# Arduino.net
KiCad netlist of a schematic drawn in EasyEDA Pro
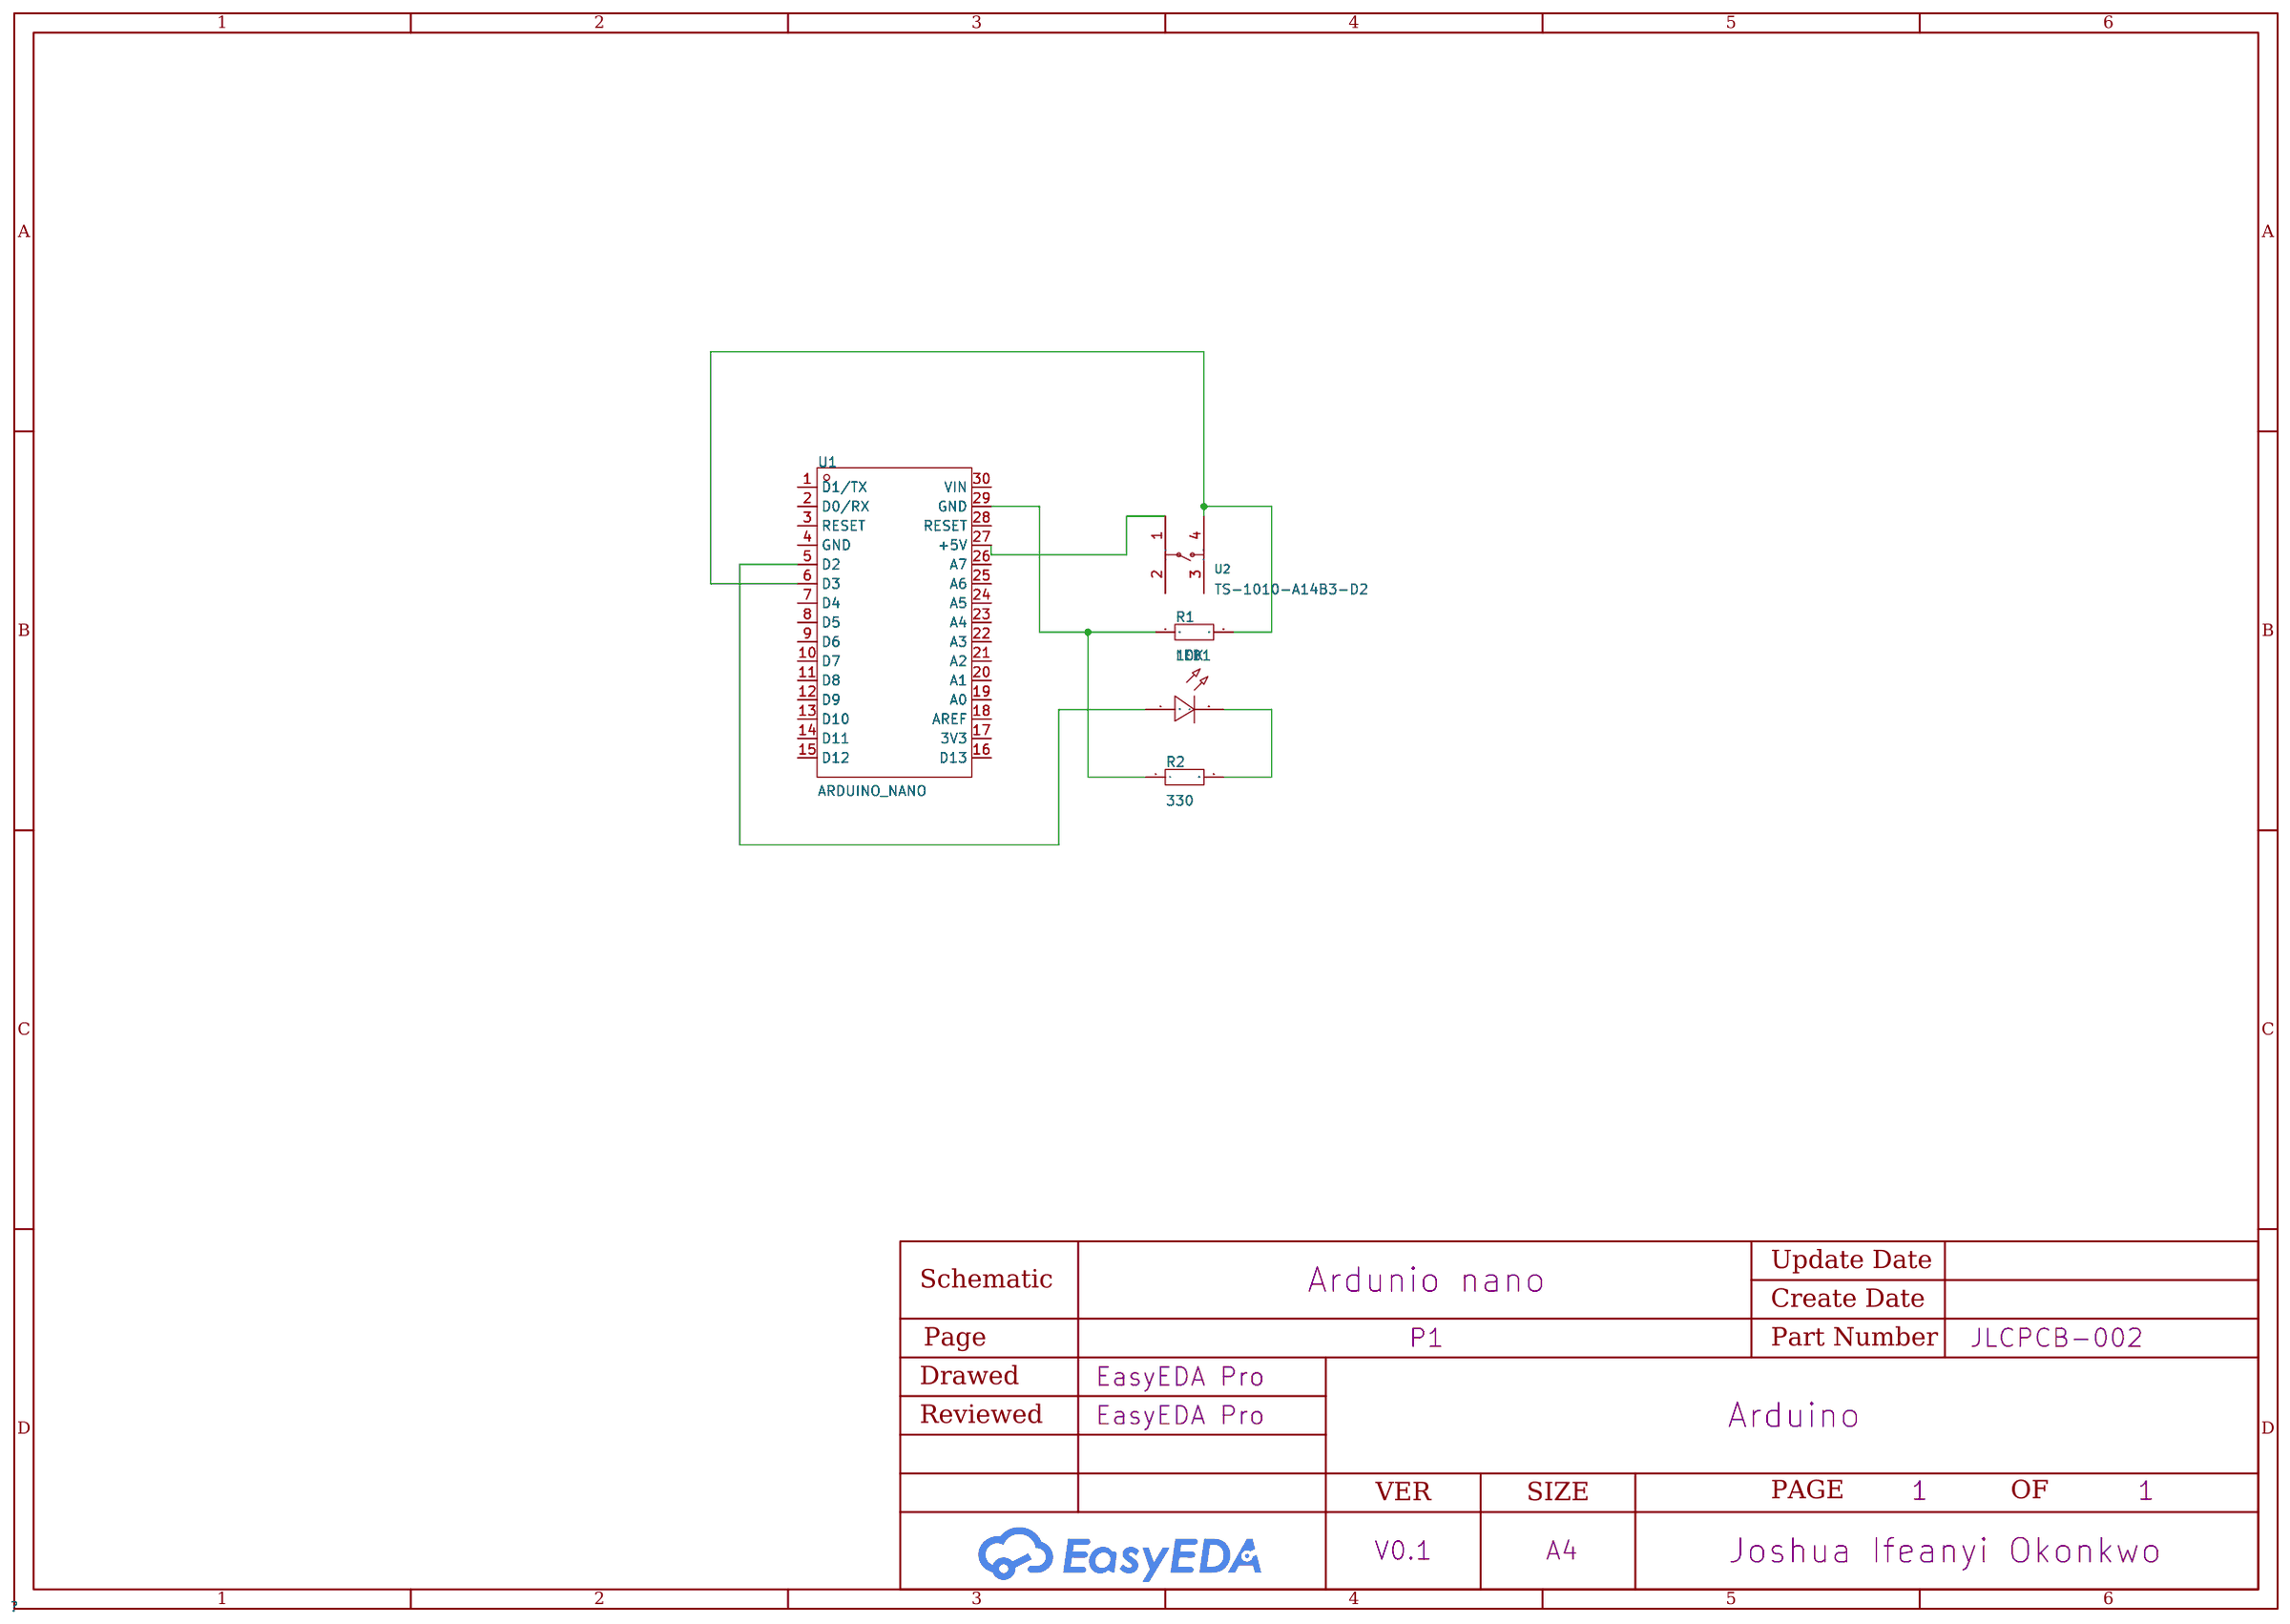
[diagram p0: schematic sheet]

(export (version "E")
  (design (tool "Eeschema 10.0.6"))
  (components
    (comp (ref "LED1")
      (value "~")
      (footprint "easyedapro:LED-TH_BD3.0-P2.54-FD")
      (libsource (lib "easyedapro") (part "LED_TH-R"))
    )
    (comp (ref "R1") (value "10K") (footprint "easyedapro:R0603") (libsource (lib "easyedapro") (part "Res")))
    (comp (ref "R2") (value "330") (footprint "easyedapro:R0603") (libsource (lib "easyedapro") (part "Res")))
    (comp (ref "U1")
      (value "ARDUINO_NANO")
      (footprint "easyedapro:COMM-TH_ARDUINO_NANO")
      (libsource (lib "easyedapro") (part "ARDUINO_NANO"))
    )
    (comp (ref "U2")
      (value "TS-1010-A14B3-D2")
      (footprint "easyedapro:SW-TH_4P-L6.2-W6.2-P4.50-LS6.5")
      (fields (field (name "Manufacturer") "Yuandi(元迪)"))
      (libsource (lib "easyedapro") (part "TS-1010-A14B3-D2"))
    )
  )
  (nets
    (net (code "1") (name "Net-(LED1-A)") (class "Default")
      (node (ref "LED1") (pin "2") (pinfunction "A_2") (pintype "input"))
      (node (ref "R2") (pin "2") (pinfunction "2_2") (pintype "input"))
    )
    (net (code "2") (name "Net-(LED1-C)") (class "Default")
      (node (ref "LED1") (pin "1") (pinfunction "C_1") (pintype "input"))
      (node (ref "U1") (pin "5") (pinfunction "D2_5") (pintype "input"))
    )
    (net (code "3") (name "Net-(R1-Pad1)") (class "Default")
      (node (ref "R1") (pin "1") (pinfunction "1_1") (pintype "input"))
      (node (ref "R2") (pin "1") (pinfunction "1_1") (pintype "input"))
      (node (ref "U1") (pin "29") (pinfunction "GND_29") (pintype "input"))
    )
    (net (code "4") (name "Net-(U1-+5V)") (class "Default")
      (node (ref "U1") (pin "27") (pinfunction "+5V_27") (pintype "input"))
      (node (ref "U2") (pin "1") (pinfunction "1_1") (pintype "input"))
    )
    (net (code "5") (name "Net-(U1-D3)") (class "Default")
      (node (ref "R1") (pin "2") (pinfunction "2_2") (pintype "input"))
      (node (ref "U1") (pin "6") (pinfunction "D3_6") (pintype "input"))
      (node (ref "U2") (pin "4") (pinfunction "4_4") (pintype "input"))
    )
    (net (code "6") (name "unconnected-(U1-3V3-Pad17)") (class "Default")
      (node (ref "U1") (pin "17") (pinfunction "3V3_17") (pintype "input"))
    )
    (net (code "7") (name "unconnected-(U1-A0-Pad19)") (class "Default")
      (node (ref "U1") (pin "19") (pinfunction "A0_19") (pintype "input"))
    )
    (net (code "8") (name "unconnected-(U1-A1-Pad20)") (class "Default")
      (node (ref "U1") (pin "20") (pinfunction "A1_20") (pintype "input"))
    )
    (net (code "9") (name "unconnected-(U1-A2-Pad21)") (class "Default")
      (node (ref "U1") (pin "21") (pinfunction "A2_21") (pintype "input"))
    )
    (net (code "10") (name "unconnected-(U1-A3-Pad22)") (class "Default")
      (node (ref "U1") (pin "22") (pinfunction "A3_22") (pintype "input"))
    )
    (net (code "11") (name "unconnected-(U1-A4-Pad23)") (class "Default")
      (node (ref "U1") (pin "23") (pinfunction "A4_23") (pintype "input"))
    )
    (net (code "12") (name "unconnected-(U1-A5-Pad24)") (class "Default")
      (node (ref "U1") (pin "24") (pinfunction "A5_24") (pintype "input"))
    )
    (net (code "13") (name "unconnected-(U1-A6-Pad25)") (class "Default")
      (node (ref "U1") (pin "25") (pinfunction "A6_25") (pintype "input"))
    )
    (net (code "14") (name "unconnected-(U1-A7-Pad26)") (class "Default")
      (node (ref "U1") (pin "26") (pinfunction "A7_26") (pintype "input"))
    )
    (net (code "15") (name "unconnected-(U1-AREF-Pad18)") (class "Default")
      (node (ref "U1") (pin "18") (pinfunction "AREF_18") (pintype "input"))
    )
    (net (code "16") (name "unconnected-(U1-D0{slash}RX-Pad2)") (class "Default")
      (node (ref "U1") (pin "2") (pinfunction "D0/RX_2") (pintype "input"))
    )
    (net (code "17") (name "unconnected-(U1-D1{slash}TX-Pad1)") (class "Default")
      (node (ref "U1") (pin "1") (pinfunction "D1/TX_1") (pintype "input"))
    )
    (net (code "18") (name "unconnected-(U1-D4-Pad7)") (class "Default")
      (node (ref "U1") (pin "7") (pinfunction "D4_7") (pintype "input"))
    )
    (net (code "19") (name "unconnected-(U1-D5-Pad8)") (class "Default")
      (node (ref "U1") (pin "8") (pinfunction "D5_8") (pintype "input"))
    )
    (net (code "20") (name "unconnected-(U1-D6-Pad9)") (class "Default")
      (node (ref "U1") (pin "9") (pinfunction "D6_9") (pintype "input"))
    )
    (net (code "21") (name "unconnected-(U1-D7-Pad10)") (class "Default")
      (node (ref "U1") (pin "10") (pinfunction "D7_10") (pintype "input"))
    )
    (net (code "22") (name "unconnected-(U1-D8-Pad11)") (class "Default")
      (node (ref "U1") (pin "11") (pinfunction "D8_11") (pintype "input"))
    )
    (net (code "23") (name "unconnected-(U1-D9-Pad12)") (class "Default")
      (node (ref "U1") (pin "12") (pinfunction "D9_12") (pintype "input"))
    )
    (net (code "24") (name "unconnected-(U1-D10-Pad13)") (class "Default")
      (node (ref "U1") (pin "13") (pinfunction "D10_13") (pintype "input"))
    )
    (net (code "25") (name "unconnected-(U1-D11-Pad14)") (class "Default")
      (node (ref "U1") (pin "14") (pinfunction "D11_14") (pintype "input"))
    )
    (net (code "26") (name "unconnected-(U1-D12-Pad15)") (class "Default")
      (node (ref "U1") (pin "15") (pinfunction "D12_15") (pintype "input"))
    )
    (net (code "27") (name "unconnected-(U1-D13-Pad16)") (class "Default")
      (node (ref "U1") (pin "16") (pinfunction "D13_16") (pintype "input"))
    )
    (net (code "28") (name "unconnected-(U1-GND-Pad4)") (class "Default")
      (node (ref "U1") (pin "4") (pinfunction "GND_4") (pintype "input"))
    )
    (net (code "29") (name "unconnected-(U1-RESET-Pad3)") (class "Default")
      (node (ref "U1") (pin "3") (pinfunction "RESET_3") (pintype "input"))
    )
    (net (code "30") (name "unconnected-(U1-RESET-Pad28)") (class "Default")
      (node (ref "U1") (pin "28") (pinfunction "RESET_28") (pintype "input"))
    )
    (net (code "31") (name "unconnected-(U1-VIN-Pad30)") (class "Default")
      (node (ref "U1") (pin "30") (pinfunction "VIN_30") (pintype "input"))
    )
    (net (code "32") (name "unconnected-(U2-Pad2)") (class "Default")
      (node (ref "U2") (pin "2") (pinfunction "2_2") (pintype "input"))
    )
    (net (code "33") (name "unconnected-(U2-Pad3)") (class "Default")
      (node (ref "U2") (pin "3") (pinfunction "3_3") (pintype "input"))
    )
  )
)
